# STRWHL-S06-V00-Interface.net
KiCad netlist of a schematic drawn in Altium Designer
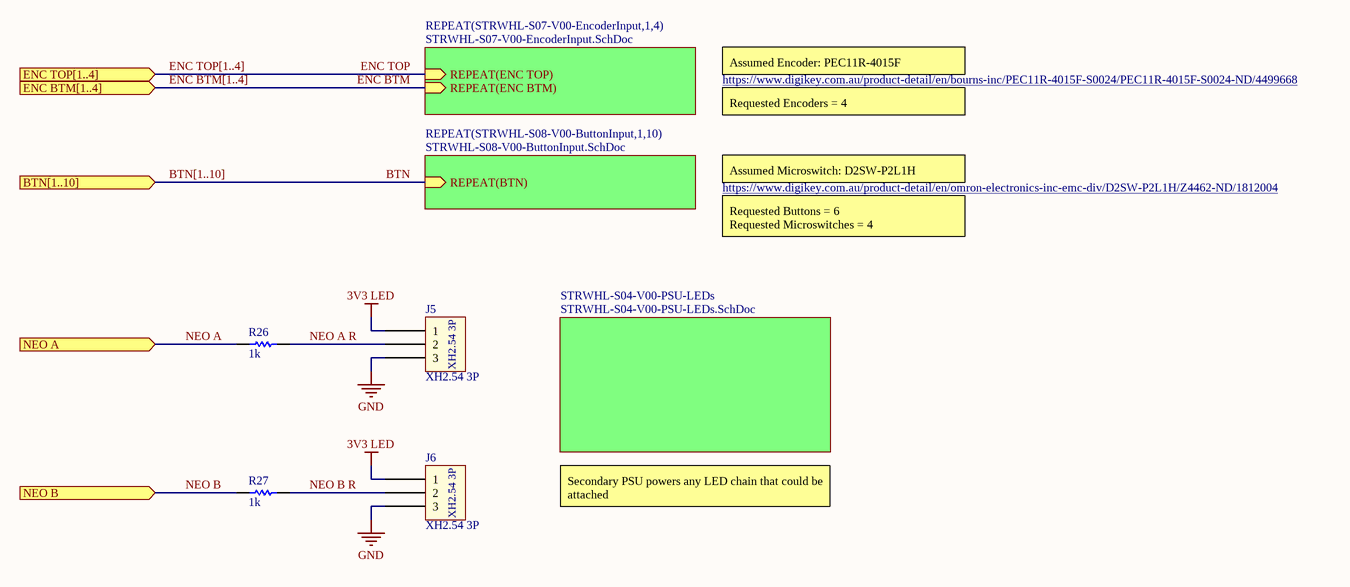
[diagram p0: STRWHL-S06-V00-Interface.SchDoc]

(export (version "E")
  (design (tool "Eeschema 10.0.6"))
  (components
    (comp (ref "J5")
      (value "XH2.54 3P")
      (footprint "JST_XH254_3P_TH_RH")
      (libsource (lib "JST_XH254") (part "XH2.54 3P"))
    )
    (comp (ref "J6")
      (value "XH2.54 3P")
      (footprint "JST_XH254_3P_TH_RH")
      (libsource (lib "JST_XH254") (part "XH2.54 3P"))
    )
    (comp (ref "R26")
      (value "1k")
      (footprint "Res_ThinFilm_0603")
      (description "Resistor, SMD, 1k, 0.1W, 5%, 0603")
      (libsource (lib "StandardResistors") (part "1k 5% 0603"))
    )
    (comp (ref "R27")
      (value "1k")
      (footprint "Res_ThinFilm_0603")
      (description "Resistor, SMD, 1k, 0.1W, 5%, 0603")
      (libsource (lib "StandardResistors") (part "1k 5% 0603"))
    )
  )
  (nets
    (net (code "15") (name "/NEO A") (class "Default")
      (node (ref "R26") (pin "1") (pinfunction "1_1") (pintype "passive"))
    )
    (net (code "16") (name "/NEO A R") (class "Default")
      (node (ref "J5") (pin "2") (pinfunction "2_2") (pintype "passive"))
      (node (ref "R26") (pin "2") (pinfunction "2_2") (pintype "passive"))
    )
    (net (code "17") (name "/NEO B") (class "Default")
      (node (ref "R27") (pin "1") (pinfunction "1_1") (pintype "passive"))
    )
    (net (code "18") (name "/NEO B R") (class "Default")
      (node (ref "J6") (pin "2") (pinfunction "2_2") (pintype "passive"))
      (node (ref "R27") (pin "2") (pinfunction "2_2") (pintype "passive"))
    )
    (net (code "21") (name "3V3 LED") (class "Default")
      (node (ref "J5") (pin "1") (pinfunction "1_1") (pintype "passive"))
      (node (ref "J6") (pin "1") (pinfunction "1_1") (pintype "passive"))
    )
    (net (code "22") (name "GND") (class "Default")
      (node (ref "J5") (pin "3") (pinfunction "3_3") (pintype "passive"))
      (node (ref "J6") (pin "3") (pinfunction "3_3") (pintype "passive"))
    )
  )
)
